# CAN-Junction.net
KiCad netlist of a schematic drawn in Altium Designer
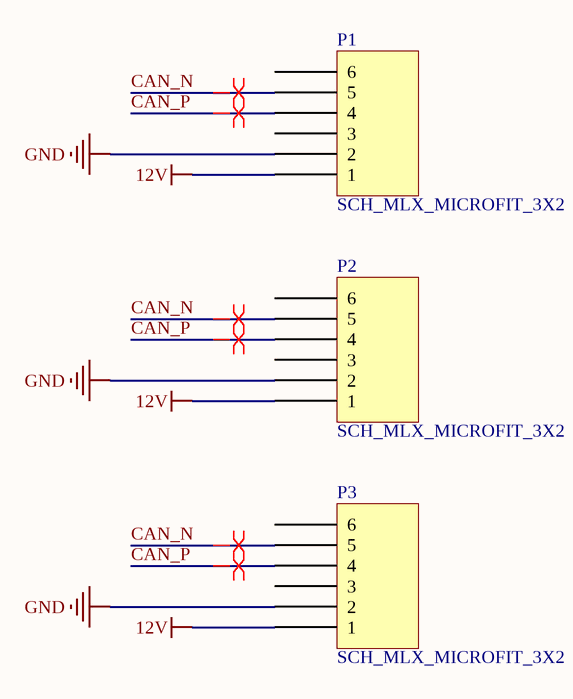
[diagram p0: CAN-Junction.SchDoc]

(export (version "E")
  (design (tool "Eeschema 10.0.6"))
  (components
    (comp (ref "P1")
      (value "SCH_MLX_MICROFIT_3X2")
      (footprint "PCB_MLX_MICROFIT_3X2")
      (libsource (lib "Molex Microfit 3.0 3x2") (part "SCH_MLX_MICROFIT_3X2"))
    )
    (comp (ref "P2")
      (value "SCH_MLX_MICROFIT_3X2")
      (footprint "PCB_MLX_MICROFIT_3X2")
      (libsource (lib "Molex Microfit 3.0 3x2") (part "SCH_MLX_MICROFIT_3X2"))
    )
    (comp (ref "P3")
      (value "SCH_MLX_MICROFIT_3X2")
      (footprint "PCB_MLX_MICROFIT_3X2")
      (libsource (lib "Molex Microfit 3.0 3x2") (part "SCH_MLX_MICROFIT_3X2"))
    )
  )
  (nets
    (net (code "1") (name "/CAN_N") (class "Default")
      (node (ref "P1") (pin "5") (pinfunction "5_5") (pintype "passive"))
      (node (ref "P2") (pin "5") (pinfunction "5_5") (pintype "passive"))
      (node (ref "P3") (pin "5") (pinfunction "5_5") (pintype "passive"))
    )
    (net (code "2") (name "/CAN_P") (class "Default")
      (node (ref "P1") (pin "4") (pinfunction "4_4") (pintype "passive"))
      (node (ref "P2") (pin "4") (pinfunction "4_4") (pintype "passive"))
      (node (ref "P3") (pin "4") (pinfunction "4_4") (pintype "passive"))
    )
    (net (code "3") (name "12V") (class "Default")
      (node (ref "P1") (pin "1") (pinfunction "1_1") (pintype "passive"))
      (node (ref "P2") (pin "1") (pinfunction "1_1") (pintype "passive"))
      (node (ref "P3") (pin "1") (pinfunction "1_1") (pintype "passive"))
    )
    (net (code "4") (name "GND") (class "Default")
      (node (ref "P1") (pin "2") (pinfunction "2_2") (pintype "passive"))
      (node (ref "P2") (pin "2") (pinfunction "2_2") (pintype "passive"))
      (node (ref "P3") (pin "2") (pinfunction "2_2") (pintype "passive"))
    )
    (net (code "5") (name "unconnected-(P1-Pad3)") (class "Default")
      (node (ref "P1") (pin "3") (pinfunction "3_3") (pintype "passive"))
    )
    (net (code "6") (name "unconnected-(P1-Pad6)") (class "Default")
      (node (ref "P1") (pin "6") (pinfunction "6_6") (pintype "passive"))
    )
    (net (code "7") (name "unconnected-(P2-Pad3)") (class "Default")
      (node (ref "P2") (pin "3") (pinfunction "3_3") (pintype "passive"))
    )
    (net (code "8") (name "unconnected-(P2-Pad6)") (class "Default")
      (node (ref "P2") (pin "6") (pinfunction "6_6") (pintype "passive"))
    )
    (net (code "9") (name "unconnected-(P3-Pad3)") (class "Default")
      (node (ref "P3") (pin "3") (pinfunction "3_3") (pintype "passive"))
    )
    (net (code "10") (name "unconnected-(P3-Pad6)") (class "Default")
      (node (ref "P3") (pin "6") (pinfunction "6_6") (pintype "passive"))
    )
  )
)
